# 5V-and-3V3-buck.net
KiCad netlist of a schematic drawn in Altium Designer
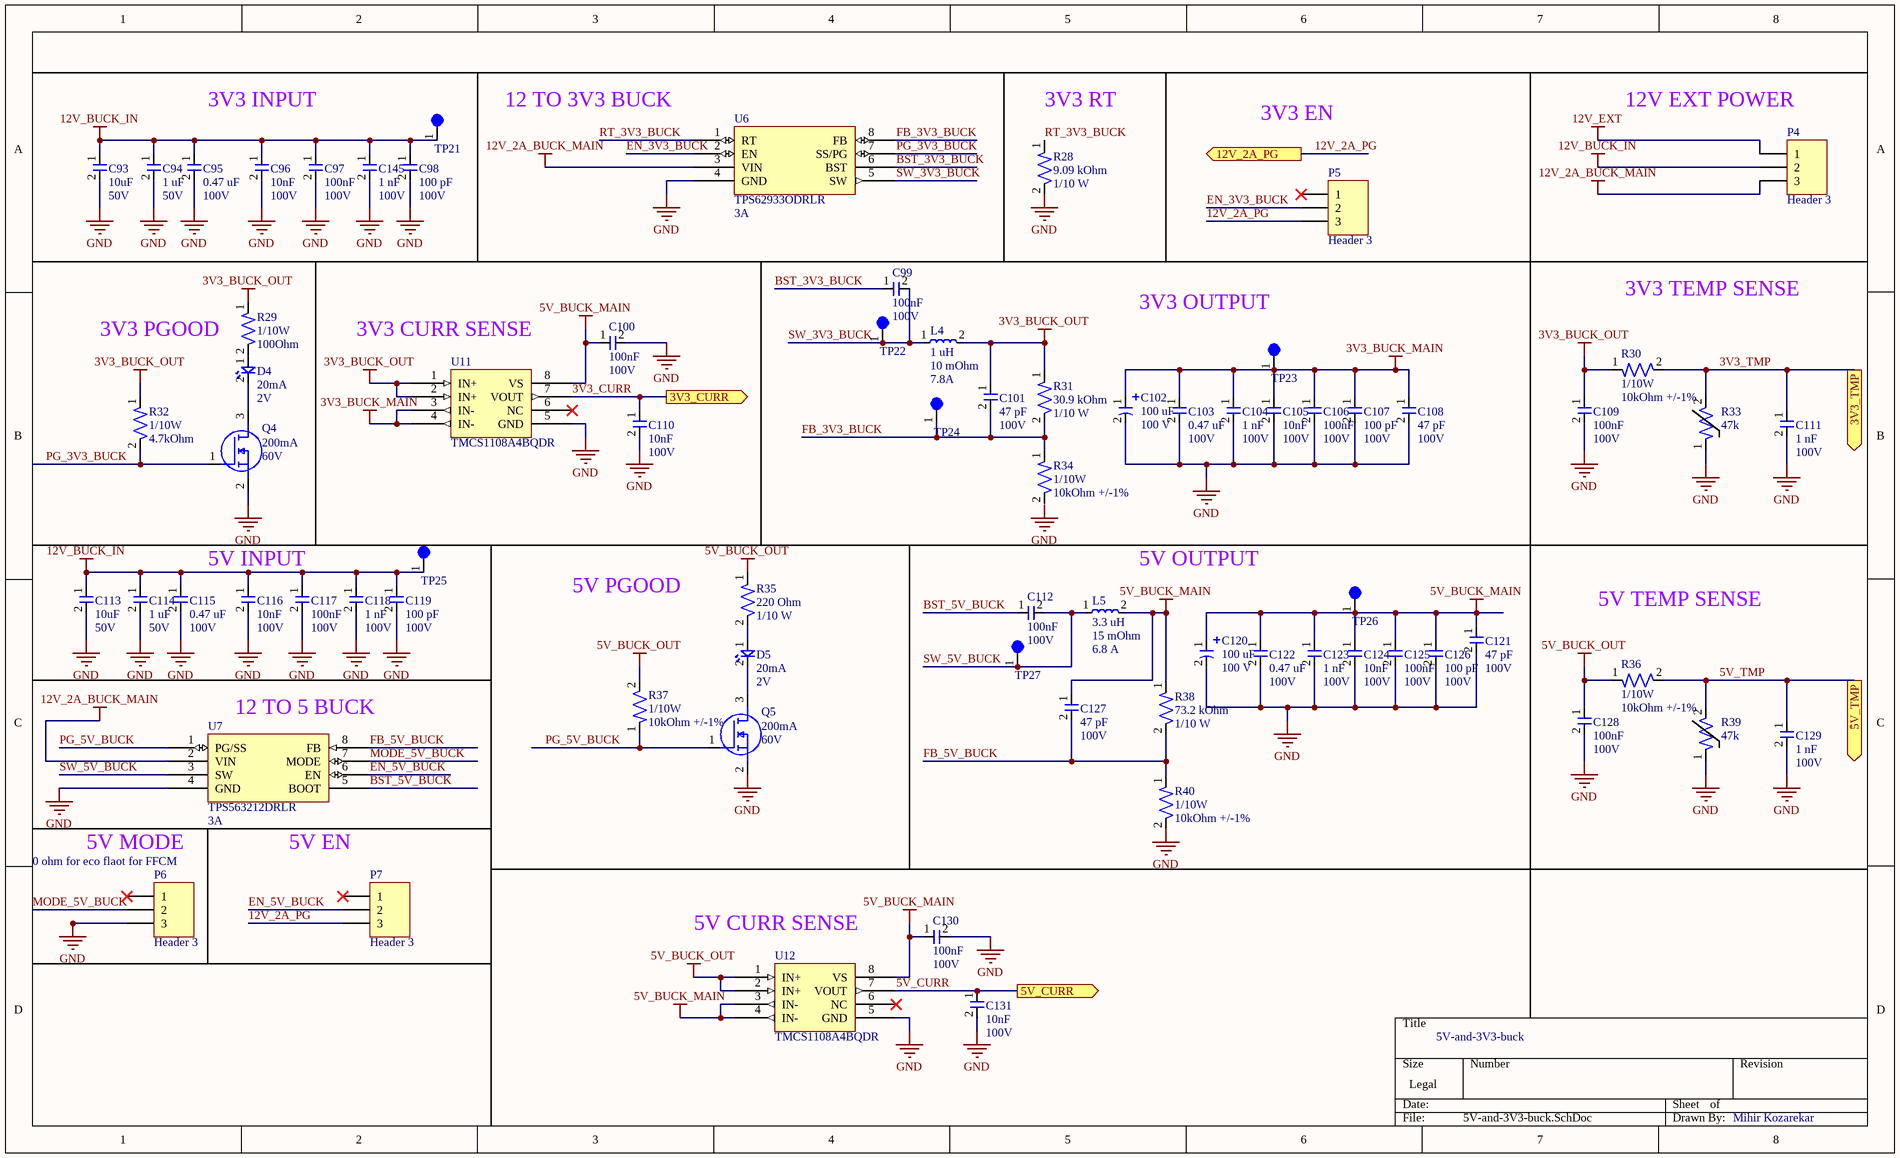
[diagram p0: 5V-and-3V3-buck.SchDoc]

(export (version "E")
  (design (tool "Eeschema 10.0.6"))
  (components
    (comp (ref "C93")
      (value "CL31B106KBHNNNE")
      (footprint "CAP-1206")
      (description "10 µF ±10% 50V Ceramic Capacitor X7R 1206 (3216 Metric)")
      (fields
        (field (name "MANUFACTURER") "Samsung Electro-Mechanics")
        (field (name "CAPACITANCE") "10uF")
        (field (name "VOLTAGE RATING") "50V")
      )
      (libsource (lib "MasterLib") (part "CAP-10U-0001"))
    )
    (comp (ref "C94")
      (value "UMK107AB7105KA-T")
      (footprint "CAP-0603")
      (description "1 µF ±10% 50V Ceramic Capacitor X7R 0603 (1608 Metric)")
      (fields (field (name "CAPACITANCE") "1 uF") (field (name "VOLTAGE") "50V"))
      (libsource (lib "MasterLib") (part "CAP-1U-0002"))
    )
    (comp (ref "C95")
      (value "KAM21KR72A474KL")
      (footprint "CAP-0805")
      (description "0.47 µF ±10% 100V Ceramic Capacitor X7R 0805 (2012 Metric)")
      (fields
        (field (name "TOLERANCE") "+/- 10%")
        (field (name "CAPACITANCE") "0.47 uF")
        (field (name "VOLTAGE") "100V")
      )
      (libsource (lib "MasterLib") (part "CAP-0.47U-0001"))
    )
    (comp (ref "C96")
      (value "C1608C0G2A103J080AC")
      (footprint "CAP-0603")
      (description "CAP CER 10000PF 100V C0G 0603")
      (fields
        (field (name "MANUFACTURER") "TDK Corporation")
        (field (name "CAPACITANCE") "10nF")
        (field (name "VOLTAGE RATING") "100V")
      )
      (libsource (lib "MasterLib") (part "CAP-10N-0002"))
    )
    (comp (ref "C97")
      (value "CC0603KRX7R0BB104")
      (footprint "CAP-0603")
      (description "CAP CER 0.1UF 100V X7R 0603")
      (fields
        (field (name "MANUFACTURER") "YAGEO")
        (field (name "CAPACITANCE") "100nF")
        (field (name "VOLTAGE RATING") "100V")
      )
      (libsource (lib "MasterLib") (part "CAP-100N-0001"))
    )
    (comp (ref "C98")
      (value "0603N101J101CT")
      (footprint "CAP-0603")
      (description "100 pF ±5% 100V Ceramic Capacitor C0G, NP0 0603 (1608 Metric)")
      (fields
        (field (name "TOLERANCE") "+/-5%")
        (field (name "CAPACITANCE") "100 pF")
        (field (name "VOLTAGE") "100V")
      )
      (libsource (lib "MasterLib") (part "CAP-100P-0002"))
    )
    (comp (ref "C99")
      (value "CC0603KRX7R0BB104")
      (footprint "CAP-0603")
      (description "CAP CER 0.1UF 100V X7R 0603")
      (fields
        (field (name "MANUFACTURER") "YAGEO")
        (field (name "CAPACITANCE") "100nF")
        (field (name "VOLTAGE RATING") "100V")
      )
      (libsource (lib "MasterLib") (part "CAP-100N-0001"))
    )
    (comp (ref "C100")
      (value "CC0603KRX7R0BB104")
      (footprint "CAP-0603")
      (description "CAP CER 0.1UF 100V X7R 0603")
      (fields
        (field (name "MANUFACTURER") "YAGEO")
        (field (name "CAPACITANCE") "100nF")
        (field (name "VOLTAGE RATING") "100V")
      )
      (libsource (lib "MasterLib") (part "CAP-100N-0001"))
    )
    (comp (ref "C101")
      (value "7447798111")
      (footprint "CAP-0603")
      (description "47 pF ±5% 100V Ceramic Capacitor C0G, NP0 0603 (1608 Metric)")
      (fields (field (name "CAPACITANCE") "47 pF") (field (name "VOLTAGE RATING") "100V"))
      (libsource (lib "MasterLib") (part "CAP-47P-0001"))
    )
    (comp (ref "C102")
      (value "100SEV100M12.5X16")
      (footprint "ELEC-100U-0001")
      (description "100 µF 100 V Aluminum Electrolytic Capacitors Radial, Can - SMD 2000 Hrs @ 85°C")
      (fields
        (field (name "MANUFACTURER") "Rubycon")
        (field (name "TOLERANCE") "+/- 20%")
        (field (name "CAPACITANCE") "100 uF")
        (field (name "VOLTAGE") "100 V")
      )
      (libsource (lib "MasterLib") (part "ELEC-100U-0001"))
    )
    (comp (ref "C103")
      (value "KAM21KR72A474KL")
      (footprint "CAP-0805")
      (description "0.47 µF ±10% 100V Ceramic Capacitor X7R 0805 (2012 Metric)")
      (fields
        (field (name "TOLERANCE") "+/- 10%")
        (field (name "CAPACITANCE") "0.47 uF")
        (field (name "VOLTAGE") "100V")
      )
      (libsource (lib "MasterLib") (part "CAP-0.47U-0001"))
    )
    (comp (ref "C104")
      (value "C0603Y102K1RAC7867")
      (footprint "CAP-0603")
      (description "1000 pF ±10% 100V Ceramic Capacitor X7R 0603 (1608 Metric)")
      (fields (field (name "CAPACITANCE") "1 nF") (field (name "VOLTAGE") "100V"))
      (libsource (lib "MasterLib") (part "CAP-1N-0001"))
    )
    (comp (ref "C105")
      (value "C1608C0G2A103J080AC")
      (footprint "CAP-0603")
      (description "CAP CER 10000PF 100V C0G 0603")
      (fields
        (field (name "MANUFACTURER") "TDK Corporation")
        (field (name "CAPACITANCE") "10nF")
        (field (name "VOLTAGE RATING") "100V")
      )
      (libsource (lib "MasterLib") (part "CAP-10N-0002"))
    )
    (comp (ref "C106")
      (value "CC0603KRX7R0BB104")
      (footprint "CAP-0603")
      (description "CAP CER 0.1UF 100V X7R 0603")
      (fields
        (field (name "MANUFACTURER") "YAGEO")
        (field (name "CAPACITANCE") "100nF")
        (field (name "VOLTAGE RATING") "100V")
      )
      (libsource (lib "MasterLib") (part "CAP-100N-0001"))
    )
    (comp (ref "C107")
      (value "0603N101J101CT")
      (footprint "CAP-0603")
      (description "100 pF ±5% 100V Ceramic Capacitor C0G, NP0 0603 (1608 Metric)")
      (fields
        (field (name "TOLERANCE") "+/-5%")
        (field (name "CAPACITANCE") "100 pF")
        (field (name "VOLTAGE") "100V")
      )
      (libsource (lib "MasterLib") (part "CAP-100P-0002"))
    )
    (comp (ref "C108")
      (value "7447798111")
      (footprint "CAP-0603")
      (description "47 pF ±5% 100V Ceramic Capacitor C0G, NP0 0603 (1608 Metric)")
      (fields (field (name "CAPACITANCE") "47 pF") (field (name "VOLTAGE RATING") "100V"))
      (libsource (lib "MasterLib") (part "CAP-47P-0001"))
    )
    (comp (ref "C109")
      (value "CC0603KRX7R0BB104")
      (footprint "CAP-0603")
      (description "CAP CER 0.1UF 100V X7R 0603")
      (fields
        (field (name "MANUFACTURER") "YAGEO")
        (field (name "CAPACITANCE") "100nF")
        (field (name "VOLTAGE RATING") "100V")
      )
      (libsource (lib "MasterLib") (part "CAP-100N-0001"))
    )
    (comp (ref "C110")
      (value "C1608C0G2A103J080AC")
      (footprint "CAP-0603")
      (description "CAP CER 10000PF 100V C0G 0603")
      (fields
        (field (name "MANUFACTURER") "TDK Corporation")
        (field (name "CAPACITANCE") "10nF")
        (field (name "VOLTAGE RATING") "100V")
      )
      (libsource (lib "MasterLib") (part "CAP-10N-0002"))
    )
    (comp (ref "C111")
      (value "C0603Y102K1RAC7867")
      (footprint "CAP-0603")
      (description "1000 pF ±10% 100V Ceramic Capacitor X7R 0603 (1608 Metric)")
      (fields (field (name "CAPACITANCE") "1 nF") (field (name "VOLTAGE") "100V"))
      (libsource (lib "MasterLib") (part "CAP-1N-0001"))
    )
    (comp (ref "C112")
      (value "CC0603KRX7R0BB104")
      (footprint "CAP-0603")
      (description "CAP CER 0.1UF 100V X7R 0603")
      (fields
        (field (name "MANUFACTURER") "YAGEO")
        (field (name "CAPACITANCE") "100nF")
        (field (name "VOLTAGE RATING") "100V")
      )
      (libsource (lib "MasterLib") (part "CAP-100N-0001"))
    )
    (comp (ref "C113")
      (value "CL31B106KBHNNNE")
      (footprint "CAP-1206")
      (description "10 µF ±10% 50V Ceramic Capacitor X7R 1206 (3216 Metric)")
      (fields
        (field (name "MANUFACTURER") "Samsung Electro-Mechanics")
        (field (name "CAPACITANCE") "10uF")
        (field (name "VOLTAGE RATING") "50V")
      )
      (libsource (lib "MasterLib") (part "CAP-10U-0001"))
    )
    (comp (ref "C114")
      (value "UMK107AB7105KA-T")
      (footprint "CAP-0603")
      (description "1 µF ±10% 50V Ceramic Capacitor X7R 0603 (1608 Metric)")
      (fields (field (name "CAPACITANCE") "1 uF") (field (name "VOLTAGE") "50V"))
      (libsource (lib "MasterLib") (part "CAP-1U-0002"))
    )
    (comp (ref "C115")
      (value "KAM21KR72A474KL")
      (footprint "CAP-0805")
      (description "0.47 µF ±10% 100V Ceramic Capacitor X7R 0805 (2012 Metric)")
      (fields
        (field (name "TOLERANCE") "+/- 10%")
        (field (name "CAPACITANCE") "0.47 uF")
        (field (name "VOLTAGE") "100V")
      )
      (libsource (lib "MasterLib") (part "CAP-0.47U-0001"))
    )
    (comp (ref "C116")
      (value "C1608C0G2A103J080AC")
      (footprint "CAP-0603")
      (description "CAP CER 10000PF 100V C0G 0603")
      (fields
        (field (name "MANUFACTURER") "TDK Corporation")
        (field (name "CAPACITANCE") "10nF")
        (field (name "VOLTAGE RATING") "100V")
      )
      (libsource (lib "MasterLib") (part "CAP-10N-0002"))
    )
    (comp (ref "C117")
      (value "CC0603KRX7R0BB104")
      (footprint "CAP-0603")
      (description "CAP CER 0.1UF 100V X7R 0603")
      (fields
        (field (name "MANUFACTURER") "YAGEO")
        (field (name "CAPACITANCE") "100nF")
        (field (name "VOLTAGE RATING") "100V")
      )
      (libsource (lib "MasterLib") (part "CAP-100N-0001"))
    )
    (comp (ref "C118")
      (value "C0603Y102K1RAC7867")
      (footprint "CAP-0603")
      (description "1000 pF ±10% 100V Ceramic Capacitor X7R 0603 (1608 Metric)")
      (fields (field (name "CAPACITANCE") "1 nF") (field (name "VOLTAGE") "100V"))
      (libsource (lib "MasterLib") (part "CAP-1N-0001"))
    )
    (comp (ref "C119")
      (value "0603N101J101CT")
      (footprint "CAP-0603")
      (description "100 pF ±5% 100V Ceramic Capacitor C0G, NP0 0603 (1608 Metric)")
      (fields
        (field (name "TOLERANCE") "+/-5%")
        (field (name "CAPACITANCE") "100 pF")
        (field (name "VOLTAGE") "100V")
      )
      (libsource (lib "MasterLib") (part "CAP-100P-0002"))
    )
    (comp (ref "C120")
      (value "100SEV100M12.5X16")
      (footprint "ELEC-100U-0001")
      (description "100 µF 100 V Aluminum Electrolytic Capacitors Radial, Can - SMD 2000 Hrs @ 85°C")
      (fields
        (field (name "MANUFACTURER") "Rubycon")
        (field (name "TOLERANCE") "+/- 20%")
        (field (name "CAPACITANCE") "100 uF")
        (field (name "VOLTAGE") "100 V")
      )
      (libsource (lib "MasterLib") (part "ELEC-100U-0001"))
    )
    (comp (ref "C121")
      (value "7447798111")
      (footprint "CAP-0603")
      (description "47 pF ±5% 100V Ceramic Capacitor C0G, NP0 0603 (1608 Metric)")
      (fields (field (name "CAPACITANCE") "47 pF") (field (name "VOLTAGE RATING") "100V"))
      (libsource (lib "MasterLib") (part "CAP-47P-0001"))
    )
    (comp (ref "C122")
      (value "KAM21KR72A474KL")
      (footprint "CAP-0805")
      (description "0.47 µF ±10% 100V Ceramic Capacitor X7R 0805 (2012 Metric)")
      (fields
        (field (name "TOLERANCE") "+/- 10%")
        (field (name "CAPACITANCE") "0.47 uF")
        (field (name "VOLTAGE") "100V")
      )
      (libsource (lib "MasterLib") (part "CAP-0.47U-0001"))
    )
    (comp (ref "C123")
      (value "C0603Y102K1RAC7867")
      (footprint "CAP-0603")
      (description "1000 pF ±10% 100V Ceramic Capacitor X7R 0603 (1608 Metric)")
      (fields (field (name "CAPACITANCE") "1 nF") (field (name "VOLTAGE") "100V"))
      (libsource (lib "MasterLib") (part "CAP-1N-0001"))
    )
    (comp (ref "C124")
      (value "C1608C0G2A103J080AC")
      (footprint "CAP-0603")
      (description "CAP CER 10000PF 100V C0G 0603")
      (fields
        (field (name "MANUFACTURER") "TDK Corporation")
        (field (name "CAPACITANCE") "10nF")
        (field (name "VOLTAGE RATING") "100V")
      )
      (libsource (lib "MasterLib") (part "CAP-10N-0002"))
    )
    (comp (ref "C125")
      (value "CC0603KRX7R0BB104")
      (footprint "CAP-0603")
      (description "CAP CER 0.1UF 100V X7R 0603")
      (fields
        (field (name "MANUFACTURER") "YAGEO")
        (field (name "CAPACITANCE") "100nF")
        (field (name "VOLTAGE RATING") "100V")
      )
      (libsource (lib "MasterLib") (part "CAP-100N-0001"))
    )
    (comp (ref "C126")
      (value "0603N101J101CT")
      (footprint "CAP-0603")
      (description "100 pF ±5% 100V Ceramic Capacitor C0G, NP0 0603 (1608 Metric)")
      (fields
        (field (name "TOLERANCE") "+/-5%")
        (field (name "CAPACITANCE") "100 pF")
        (field (name "VOLTAGE") "100V")
      )
      (libsource (lib "MasterLib") (part "CAP-100P-0002"))
    )
    (comp (ref "C127")
      (value "7447798111")
      (footprint "CAP-0603")
      (description "47 pF ±5% 100V Ceramic Capacitor C0G, NP0 0603 (1608 Metric)")
      (fields (field (name "CAPACITANCE") "47 pF") (field (name "VOLTAGE RATING") "100V"))
      (libsource (lib "MasterLib") (part "CAP-47P-0001"))
    )
    (comp (ref "C128")
      (value "CC0603KRX7R0BB104")
      (footprint "CAP-0603")
      (description "CAP CER 0.1UF 100V X7R 0603")
      (fields
        (field (name "MANUFACTURER") "YAGEO")
        (field (name "CAPACITANCE") "100nF")
        (field (name "VOLTAGE RATING") "100V")
      )
      (libsource (lib "MasterLib") (part "CAP-100N-0001"))
    )
    (comp (ref "C129")
      (value "C0603Y102K1RAC7867")
      (footprint "CAP-0603")
      (description "1000 pF ±10% 100V Ceramic Capacitor X7R 0603 (1608 Metric)")
      (fields (field (name "CAPACITANCE") "1 nF") (field (name "VOLTAGE") "100V"))
      (libsource (lib "MasterLib") (part "CAP-1N-0001"))
    )
    (comp (ref "C130")
      (value "CC0603KRX7R0BB104")
      (footprint "CAP-0603")
      (description "CAP CER 0.1UF 100V X7R 0603")
      (fields
        (field (name "MANUFACTURER") "YAGEO")
        (field (name "CAPACITANCE") "100nF")
        (field (name "VOLTAGE RATING") "100V")
      )
      (libsource (lib "MasterLib") (part "CAP-100N-0001"))
    )
    (comp (ref "C131")
      (value "C1608C0G2A103J080AC")
      (footprint "CAP-0603")
      (description "CAP CER 10000PF 100V C0G 0603")
      (fields
        (field (name "MANUFACTURER") "TDK Corporation")
        (field (name "CAPACITANCE") "10nF")
        (field (name "VOLTAGE RATING") "100V")
      )
      (libsource (lib "MasterLib") (part "CAP-10N-0002"))
    )
    (comp (ref "C145")
      (value "C0603Y102K1RAC7867")
      (footprint "CAP-0603")
      (description "1000 pF ±10% 100V Ceramic Capacitor X7R 0603 (1608 Metric)")
      (fields (field (name "CAPACITANCE") "1 nF") (field (name "VOLTAGE") "100V"))
      (libsource (lib "MasterLib") (part "CAP-1N-0001"))
    )
    (comp (ref "D4")
      (value "150060AS75000")
      (footprint "LED-0603")
      (description "CAP CER 0.1UF 100V X7R 0603")
      (fields
        (field (name "MANUFACTURER") "Wurth Electronik")
        (field (name "CURRENT RATING") "20mA")
        (field (name "VF") "2V")
      )
      (libsource (lib "MasterLib") (part "LED_Amber_0001"))
    )
    (comp (ref "D5")
      (value "150060AS75000")
      (footprint "LED-0603")
      (description "CAP CER 0.1UF 100V X7R 0603")
      (fields
        (field (name "MANUFACTURER") "Wurth Electronik")
        (field (name "CURRENT RATING") "20mA")
        (field (name "VF") "2V")
      )
      (libsource (lib "MasterLib") (part "LED_Amber_0001"))
    )
    (comp (ref "L4")
      (value "SRN8040-1R0Y")
      (footprint "PWRIND-6.8U-0001")
      (description "1 µH Semi-Shielded Drum Core, Wirewound Inductor 7.8 A 10mOhm Max Nonstandard")
      (fields
        (field (name "TOLERANCE") "30%")
        (field (name "INDUCTANCE") "1 uH")
        (field (name "DCR") "10 mOhm")
        (field (name "DCI") "7.8A")
      )
      (libsource (lib "MasterLib") (part "PWRIND-1U-0001"))
    )
    (comp (ref "L5")
      (value "SRR1240-3R3Y")
      (footprint "PWRIND-3.3U-0003")
      (description "3.3 µH Shielded Drum Core, Wirewound Inductor 6.8 A 15mOhm Max Nonstandard")
      (fields
        (field (name "TOLERANCE") "30%")
        (field (name "INDUCTANCE") "3.3 uH")
        (field (name "DCR") "15 mOhm")
        (field (name "DCI") "6.8 A")
      )
      (libsource (lib "MasterLib") (part "PWRIND-3.3U-0003"))
    )
    (comp (ref "P4")
      (value "Header 3")
      (footprint "HDR1X3")
      (description "Header, 3-Pin")
      (fields (field (name "PUBLISHER") "Altium Limited"))
      (libsource (lib "Miscellaneous Connectors") (part "Header 3"))
    )
    (comp (ref "P5")
      (value "Header 3")
      (footprint "HDR1X3")
      (description "Header, 3-Pin")
      (fields (field (name "PUBLISHER") "Altium Limited"))
      (libsource (lib "Miscellaneous Connectors") (part "Header 3"))
    )
    (comp (ref "P6")
      (value "Header 3")
      (footprint "HDR1X3")
      (description "Header, 3-Pin")
      (fields (field (name "PUBLISHER") "Altium Limited"))
      (libsource (lib "Miscellaneous Connectors") (part "Header 3"))
    )
    (comp (ref "P7")
      (value "Header 3")
      (footprint "HDR1X3")
      (description "Header, 3-Pin")
      (fields (field (name "PUBLISHER") "Altium Limited"))
      (libsource (lib "Miscellaneous Connectors") (part "Header 3"))
    )
    (comp (ref "Q4")
      (value "T2N7002AK,LM")
      (footprint "NMOS-SOT23-3")
      (description "MOSFET N-CH 60V 200MA SOT23")
      (fields
        (field (name "MANUFACTURER") "Toshiba")
        (field (name "ID-CONTINUOUS") "200mA")
        (field (name "VDS-MAX") "60V")
      )
      (libsource (lib "MasterLib") (part "NMOS-200MA-0001"))
    )
    (comp (ref "Q5")
      (value "T2N7002AK,LM")
      (footprint "NMOS-SOT23-3")
      (description "MOSFET N-CH 60V 200MA SOT23")
      (fields
        (field (name "MANUFACTURER") "Toshiba")
        (field (name "ID-CONTINUOUS") "200mA")
        (field (name "VDS-MAX") "60V")
      )
      (libsource (lib "MasterLib") (part "NMOS-200MA-0001"))
    )
    (comp (ref "R28")
      (value "RC0603FR-079K09L")
      (footprint "RES-0603")
      (description "9.09 kOhms ±1% 0.1W, 1/10W Chip Resistor 0603 (1608 Metric) Moisture Resistant Thick Film")
      (fields
        (field (name "TOLERANCE") "+/-1%")
        (field (name "RESISTANCE") "9.09 kOhm")
        (field (name "POWER") "1/10 W")
      )
      (libsource (lib "MasterLib") (part "RES-9.09K-0001"))
    )
    (comp (ref "R29")
      (value "AC0603FR-10100RL")
      (footprint "RES-0603")
      (description "100 Ohms ±1% 0.1W, 1/10W Chip Resistor 0603 (1608 Metric) Automotive AEC-Q200 Thick Film")
      (fields
        (field (name "MANUFACTURER") "YAGEO")
        (field (name "POWER RATING") "1/10W")
        (field (name "RESISTANCE") "100Ohm")
      )
      (libsource (lib "MasterLib") (part "RES-100-0002"))
    )
    (comp (ref "R30")
      (value "RC0603FR-0710KP")
      (footprint "RES-0603")
      (description "RES SMD 10K OHM 1% 1/10W 0603")
      (fields
        (field (name "MANUFACTURER") "YAGEO")
        (field (name "POWER RATING") "1/10W")
        (field (name "RESISTANCE") "10kOhm +/-1%")
      )
      (libsource (lib "MasterLib") (part "RES-10K-0002"))
    )
    (comp (ref "R31")
      (value "RC0603FR-0730K9L")
      (footprint "RES-0603")
      (description "30.9 kOhms ±1% 0.1W, 1/10W Chip Resistor 0603 (1608 Metric) Moisture Resistant Thick Film")
      (fields
        (field (name "TOLERANCE") "1%")
        (field (name "RESISTANCE") "30.9 kOhm")
        (field (name "POWER") "1/10 W")
      )
      (libsource (lib "MasterLib") (part "RES-30.9K-0001"))
    )
    (comp (ref "R32")
      (value "AF0603FR-074K7L")
      (footprint "RES-0603")
      (description "RES SMD 4.7K OHM 1% 1/10W 0603")
      (fields
        (field (name "MANUFACTURER") "YAGEO")
        (field (name "POWER RATING") "1/10W")
        (field (name "RESISTANCE") "4.7kOhm")
      )
      (libsource (lib "MasterLib") (part "RES-4.7K-0002"))
    )
    (comp (ref "R33")
      (value "TMP6431DECR")
      (footprint "RES-0402")
      (description "PTC Thermistor 47 kOhms 0402 (1006 Metric)")
      (fields (field (name "MANUFACTURER") "Texas Instruments") (field (name "RESISTANCE") "47k"))
      (libsource (lib "MasterLib") (part "THERM-47K-0001"))
    )
    (comp (ref "R34")
      (value "RC0603FR-0710KP")
      (footprint "RES-0603")
      (description "RES SMD 10K OHM 1% 1/10W 0603")
      (fields
        (field (name "MANUFACTURER") "YAGEO")
        (field (name "POWER RATING") "1/10W")
        (field (name "RESISTANCE") "10kOhm +/-1%")
      )
      (libsource (lib "MasterLib") (part "RES-10K-0002"))
    )
    (comp (ref "R35")
      (value "CRGCQ0603J220R")
      (footprint "RES-0603")
      (fields
        (field (name "TOLERANCE") "+/- 5%")
        (field (name "RESISTANCE") "220 Ohm")
        (field (name "POWER") "1/10 W")
      )
      (libsource (lib "MasterLib") (part "RES-220-003"))
    )
    (comp (ref "R36")
      (value "RC0603FR-0710KP")
      (footprint "RES-0603")
      (description "RES SMD 10K OHM 1% 1/10W 0603")
      (fields
        (field (name "MANUFACTURER") "YAGEO")
        (field (name "POWER RATING") "1/10W")
        (field (name "RESISTANCE") "10kOhm +/-1%")
      )
      (libsource (lib "MasterLib") (part "RES-10K-0002"))
    )
    (comp (ref "R37")
      (value "RC0603FR-0710KP")
      (footprint "RES-0603")
      (description "RES SMD 10K OHM 1% 1/10W 0603")
      (fields
        (field (name "MANUFACTURER") "YAGEO")
        (field (name "POWER RATING") "1/10W")
        (field (name "RESISTANCE") "10kOhm +/-1%")
      )
      (libsource (lib "MasterLib") (part "RES-10K-0002"))
    )
    (comp (ref "R38")
      (value "RC0603FR-0773K2L")
      (footprint "RES-0603")
      (description "73.2 kOhms ±1% 0.1W, 1/10W Chip Resistor 0603 (1608 Metric) Moisture Resistant Thick Film")
      (fields
        (field (name "TOLERANCE") "1%")
        (field (name "RESISTANCE") "73.2 kOhm")
        (field (name "POWER") "1/10 W")
      )
      (libsource (lib "MasterLib") (part "RES-73.2K-0001"))
    )
    (comp (ref "R39")
      (value "TMP6431DECR")
      (footprint "RES-0402")
      (description "PTC Thermistor 47 kOhms 0402 (1006 Metric)")
      (fields (field (name "MANUFACTURER") "Texas Instruments") (field (name "RESISTANCE") "47k"))
      (libsource (lib "MasterLib") (part "THERM-47K-0001"))
    )
    (comp (ref "R40")
      (value "RC0603FR-0710KP")
      (footprint "RES-0603")
      (description "RES SMD 10K OHM 1% 1/10W 0603")
      (fields
        (field (name "MANUFACTURER") "YAGEO")
        (field (name "POWER RATING") "1/10W")
        (field (name "RESISTANCE") "10kOhm +/-1%")
      )
      (libsource (lib "MasterLib") (part "RES-10K-0002"))
    )
    (comp (ref "TP21")
      (value "5003")
      (footprint "TEST-POINT-0001")
      (description "Oranange PC Test Point, Miniature Phoisphor Bronze Silver Plating Through Hole Mounting Type")
      (libsource (lib "MasterLib") (part "TEST-POINT-0001"))
    )
    (comp (ref "TP22")
      (value "5003")
      (footprint "TEST-POINT-0001")
      (description "Oranange PC Test Point, Miniature Phoisphor Bronze Silver Plating Through Hole Mounting Type")
      (libsource (lib "MasterLib") (part "TEST-POINT-0001"))
    )
    (comp (ref "TP23")
      (value "5003")
      (footprint "TEST-POINT-0001")
      (description "Oranange PC Test Point, Miniature Phoisphor Bronze Silver Plating Through Hole Mounting Type")
      (libsource (lib "MasterLib") (part "TEST-POINT-0001"))
    )
    (comp (ref "TP24")
      (value "5003")
      (footprint "TEST-POINT-0001")
      (description "Oranange PC Test Point, Miniature Phoisphor Bronze Silver Plating Through Hole Mounting Type")
      (libsource (lib "MasterLib") (part "TEST-POINT-0001"))
    )
    (comp (ref "TP25")
      (value "5003")
      (footprint "TEST-POINT-0001")
      (description "Oranange PC Test Point, Miniature Phoisphor Bronze Silver Plating Through Hole Mounting Type")
      (libsource (lib "MasterLib") (part "TEST-POINT-0001"))
    )
    (comp (ref "TP26")
      (value "5003")
      (footprint "TEST-POINT-0001")
      (description "Oranange PC Test Point, Miniature Phoisphor Bronze Silver Plating Through Hole Mounting Type")
      (libsource (lib "MasterLib") (part "TEST-POINT-0001"))
    )
    (comp (ref "TP27")
      (value "5003")
      (footprint "TEST-POINT-0001")
      (description "Oranange PC Test Point, Miniature Phoisphor Bronze Silver Plating Through Hole Mounting Type")
      (libsource (lib "MasterLib") (part "TEST-POINT-0001"))
    )
    (comp (ref "U6")
      (value "TPS62933ODRLR")
      (footprint "IC-SOT583")
      (description "Buck Switching Regulator IC Positive Adjustable 0.8V 1 Output 3A SOT-583")
      (fields (field (name "MANUFACTURER") "Texas Instruments") (field (name "CURRENT") "3A"))
      (libsource (lib "MasterLib") (part "IC-BUCK-0010"))
    )
    (comp (ref "U7")
      (value "TPS563212DRLR")
      (footprint "IC-SOT583")
      (description "Buck Switching Regulator IC Positive Adjustable 0.6V 1 Output 3A SOT-583")
      (fields (field (name "MANUFACTURER") "Texaas Instruments") (field (name "CURRENT") "3A"))
      (libsource (lib "MasterLib") (part "IC-BUCK-0008"))
    )
    (comp (ref "U11")
      (value "TMCS1108A4BQDR")
      (footprint "IC-CURRENT-0001")
      (description "Current Sensor 1 Channel Hall Effect Bidirectional 8-SOIC (0.154\", 3.90mm Width)")
      (libsource (lib "MasterLib") (part "IC-CURRENT-0004"))
    )
    (comp (ref "U12")
      (value "TMCS1108A4BQDR")
      (footprint "IC-CURRENT-0001")
      (description "Current Sensor 1 Channel Hall Effect Bidirectional 8-SOIC (0.154\", 3.90mm Width)")
      (libsource (lib "MasterLib") (part "IC-CURRENT-0004"))
    )
  )
  (nets
    (net (code "1") (name "/3V3_CURR") (class "Default")
      (node (ref "C110") (pin "1") (pinfunction "1_1") (pintype "passive"))
      (node (ref "U11") (pin "7") (pinfunction "VOUT_7") (pintype "output"))
    )
    (net (code "2") (name "/3V3_TMP") (class "Default")
      (node (ref "C111") (pin "1") (pinfunction "1_1") (pintype "passive"))
      (node (ref "R30") (pin "2") (pinfunction "2_2") (pintype "passive"))
      (node (ref "R33") (pin "2") (pinfunction "2_2") (pintype "passive"))
    )
    (net (code "3") (name "/5V_CURR") (class "Default")
      (node (ref "C131") (pin "1") (pinfunction "1_1") (pintype "passive"))
      (node (ref "U12") (pin "7") (pinfunction "VOUT_7") (pintype "output"))
    )
    (net (code "4") (name "/5V_TMP") (class "Default")
      (node (ref "C129") (pin "1") (pinfunction "1_1") (pintype "passive"))
      (node (ref "R36") (pin "2") (pinfunction "2_2") (pintype "passive"))
      (node (ref "R39") (pin "2") (pinfunction "2_2") (pintype "passive"))
    )
    (net (code "5") (name "/12V_2A_PG") (class "Default")
      (node (ref "P5") (pin "3") (pinfunction "3_3") (pintype "passive"))
      (node (ref "P7") (pin "3") (pinfunction "3_3") (pintype "passive"))
    )
    (net (code "6") (name "/BST_3V3_BUCK") (class "Default")
      (node (ref "C99") (pin "1") (pinfunction "1_1") (pintype "passive"))
      (node (ref "U6") (pin "6") (pinfunction "BST_6") (pintype "power_in"))
    )
    (net (code "7") (name "/BST_5V_BUCK") (class "Default")
      (node (ref "C112") (pin "1") (pinfunction "1_1") (pintype "passive"))
      (node (ref "U7") (pin "5") (pinfunction "BOOT_5") (pintype "power_in"))
    )
    (net (code "8") (name "/EN_3V3_BUCK") (class "Default")
      (node (ref "P5") (pin "2") (pinfunction "2_2") (pintype "passive"))
      (node (ref "U6") (pin "2") (pinfunction "EN_2") (pintype "bidirectional"))
    )
    (net (code "9") (name "/EN_5V_BUCK") (class "Default")
      (node (ref "P7") (pin "2") (pinfunction "2_2") (pintype "passive"))
      (node (ref "U7") (pin "6") (pinfunction "EN_6") (pintype "bidirectional"))
    )
    (net (code "10") (name "/FB_3V3_BUCK") (class "Default")
      (node (ref "C101") (pin "2") (pinfunction "2_2") (pintype "passive"))
      (node (ref "R31") (pin "2") (pinfunction "2_2") (pintype "passive"))
      (node (ref "R34") (pin "1") (pinfunction "1_1") (pintype "passive"))
      (node (ref "TP24") (pin "1") (pinfunction "0_1") (pintype "passive"))
      (node (ref "U6") (pin "8") (pinfunction "FB_8") (pintype "bidirectional"))
    )
    (net (code "11") (name "/FB_5V_BUCK") (class "Default")
      (node (ref "C127") (pin "2") (pinfunction "2_2") (pintype "passive"))
      (node (ref "R38") (pin "2") (pinfunction "2_2") (pintype "passive"))
      (node (ref "R40") (pin "1") (pinfunction "1_1") (pintype "passive"))
      (node (ref "U7") (pin "8") (pinfunction "FB_8") (pintype "input"))
    )
    (net (code "12") (name "/MODE_5V_BUCK") (class "Default")
      (node (ref "P6") (pin "2") (pinfunction "2_2") (pintype "passive"))
      (node (ref "U7") (pin "7") (pinfunction "MODE_7") (pintype "bidirectional"))
    )
    (net (code "13") (name "/PG_3V3_BUCK") (class "Default")
      (node (ref "Q4") (pin "1") (pinfunction "G_1") (pintype "passive"))
      (node (ref "R32") (pin "2") (pinfunction "2_2") (pintype "passive"))
      (node (ref "U6") (pin "7") (pinfunction "SS/PG_7") (pintype "bidirectional"))
    )
    (net (code "14") (name "/PG_5V_BUCK") (class "Default")
      (node (ref "Q5") (pin "1") (pinfunction "G_1") (pintype "passive"))
      (node (ref "R37") (pin "1") (pinfunction "1_1") (pintype "passive"))
      (node (ref "U7") (pin "1") (pinfunction "PG/SS_1") (pintype "bidirectional"))
    )
    (net (code "15") (name "/RT_3V3_BUCK") (class "Default")
      (node (ref "R28") (pin "1") (pinfunction "1_1") (pintype "passive"))
      (node (ref "U6") (pin "1") (pinfunction "RT_1") (pintype "bidirectional"))
    )
    (net (code "16") (name "/SW_3V3_BUCK") (class "Default")
      (node (ref "C99") (pin "2") (pinfunction "2_2") (pintype "passive"))
      (node (ref "L4") (pin "1") (pinfunction "1_1") (pintype "passive"))
      (node (ref "TP22") (pin "1") (pinfunction "0_1") (pintype "passive"))
      (node (ref "U6") (pin "5") (pinfunction "SW_5") (pintype "output"))
    )
    (net (code "17") (name "/SW_5V_BUCK") (class "Default")
      (node (ref "C112") (pin "2") (pinfunction "2_2") (pintype "passive"))
      (node (ref "L5") (pin "1") (pinfunction "1_1") (pintype "passive"))
      (node (ref "TP27") (pin "1") (pinfunction "0_1") (pintype "passive"))
      (node (ref "U7") (pin "3") (pinfunction "SW_3") (pintype "power_in"))
    )
    (net (code "18") (name "3V3_BUCK_MAIN") (class "Default")
      (node (ref "C102") (pin "1") (pinfunction "1_1") (pintype "passive"))
      (node (ref "C103") (pin "1") (pinfunction "1_1") (pintype "passive"))
      (node (ref "C104") (pin "1") (pinfunction "1_1") (pintype "passive"))
      (node (ref "C105") (pin "1") (pinfunction "1_1") (pintype "passive"))
      (node (ref "C106") (pin "1") (pinfunction "1_1") (pintype "passive"))
      (node (ref "C107") (pin "1") (pinfunction "1_1") (pintype "passive"))
      (node (ref "C108") (pin "1") (pinfunction "1_1") (pintype "passive"))
      (node (ref "TP23") (pin "1") (pinfunction "0_1") (pintype "passive"))
      (node (ref "U11") (pin "3") (pinfunction "IN-_3") (pintype "output"))
      (node (ref "U11") (pin "4") (pinfunction "IN-_4") (pintype "output"))
    )
    (net (code "19") (name "3V3_BUCK_OUT") (class "Default")
      (node (ref "C101") (pin "1") (pinfunction "1_1") (pintype "passive"))
      (node (ref "C109") (pin "1") (pinfunction "1_1") (pintype "passive"))
      (node (ref "L4") (pin "2") (pinfunction "2_2") (pintype "passive"))
      (node (ref "R29") (pin "1") (pinfunction "1_1") (pintype "passive"))
      (node (ref "R30") (pin "1") (pinfunction "1_1") (pintype "passive"))
      (node (ref "R31") (pin "1") (pinfunction "1_1") (pintype "passive"))
      (node (ref "R32") (pin "1") (pinfunction "1_1") (pintype "passive"))
      (node (ref "U11") (pin "1") (pinfunction "IN+_1") (pintype "input"))
      (node (ref "U11") (pin "2") (pinfunction "IN+_2") (pintype "input"))
    )
    (net (code "20") (name "5V_BUCK_MAIN") (class "Default")
      (node (ref "C100") (pin "1") (pinfunction "1_1") (pintype "passive"))
      (node (ref "C120") (pin "1") (pinfunction "1_1") (pintype "passive"))
      (node (ref "C121") (pin "1") (pinfunction "1_1") (pintype "passive"))
      (node (ref "C122") (pin "1") (pinfunction "1_1") (pintype "passive"))
      (node (ref "C123") (pin "1") (pinfunction "1_1") (pintype "passive"))
      (node (ref "C124") (pin "1") (pinfunction "1_1") (pintype "passive"))
      (node (ref "C125") (pin "1") (pinfunction "1_1") (pintype "passive"))
      (node (ref "C126") (pin "1") (pinfunction "1_1") (pintype "passive"))
      (node (ref "C127") (pin "1") (pinfunction "1_1") (pintype "passive"))
      (node (ref "C130") (pin "1") (pinfunction "1_1") (pintype "passive"))
      (node (ref "L5") (pin "2") (pinfunction "2_2") (pintype "passive"))
      (node (ref "R38") (pin "1") (pinfunction "1_1") (pintype "passive"))
      (node (ref "TP26") (pin "1") (pinfunction "0_1") (pintype "passive"))
      (node (ref "U11") (pin "8") (pinfunction "VS_8") (pintype "power_in"))
      (node (ref "U12") (pin "3") (pinfunction "IN-_3") (pintype "output"))
      (node (ref "U12") (pin "4") (pinfunction "IN-_4") (pintype "output"))
      (node (ref "U12") (pin "8") (pinfunction "VS_8") (pintype "power_in"))
    )
    (net (code "21") (name "5V_BUCK_OUT") (class "Default")
      (node (ref "C128") (pin "1") (pinfunction "1_1") (pintype "passive"))
      (node (ref "R35") (pin "1") (pinfunction "1_1") (pintype "passive"))
      (node (ref "R36") (pin "1") (pinfunction "1_1") (pintype "passive"))
      (node (ref "R37") (pin "2") (pinfunction "2_2") (pintype "passive"))
      (node (ref "U12") (pin "1") (pinfunction "IN+_1") (pintype "input"))
      (node (ref "U12") (pin "2") (pinfunction "IN+_2") (pintype "input"))
    )
    (net (code "22") (name "12V_2A_BUCK_MAIN") (class "Default")
      (node (ref "P4") (pin "3") (pinfunction "3_3") (pintype "passive"))
      (node (ref "U6") (pin "3") (pinfunction "VIN_3") (pintype "power_in"))
      (node (ref "U7") (pin "2") (pinfunction "VIN_2") (pintype "power_in"))
    )
    (net (code "23") (name "12V_BUCK_IN") (class "Default")
      (node (ref "C113") (pin "1") (pinfunction "1_1") (pintype "passive"))
      (node (ref "C114") (pin "1") (pinfunction "1_1") (pintype "passive"))
      (node (ref "C115") (pin "1") (pinfunction "1_1") (pintype "passive"))
      (node (ref "C116") (pin "1") (pinfunction "1_1") (pintype "passive"))
      (node (ref "C117") (pin "1") (pinfunction "1_1") (pintype "passive"))
      (node (ref "C118") (pin "1") (pinfunction "1_1") (pintype "passive"))
      (node (ref "C119") (pin "1") (pinfunction "1_1") (pintype "passive"))
      (node (ref "C145") (pin "1") (pinfunction "1_1") (pintype "passive"))
      (node (ref "C93") (pin "1") (pinfunction "1_1") (pintype "passive"))
      (node (ref "C94") (pin "1") (pinfunction "1_1") (pintype "passive"))
      (node (ref "C95") (pin "1") (pinfunction "1_1") (pintype "passive"))
      (node (ref "C96") (pin "1") (pinfunction "1_1") (pintype "passive"))
      (node (ref "C97") (pin "1") (pinfunction "1_1") (pintype "passive"))
      (node (ref "C98") (pin "1") (pinfunction "1_1") (pintype "passive"))
      (node (ref "P4") (pin "2") (pinfunction "2_2") (pintype "passive"))
      (node (ref "TP21") (pin "1") (pinfunction "0_1") (pintype "passive"))
      (node (ref "TP25") (pin "1") (pinfunction "0_1") (pintype "passive"))
    )
    (net (code "24") (name "12V_EXT") (class "Default")
      (node (ref "P4") (pin "1") (pinfunction "1_1") (pintype "passive"))
    )
    (net (code "25") (name "GND") (class "Default")
      (node (ref "C100") (pin "2") (pinfunction "2_2") (pintype "passive"))
      (node (ref "C102") (pin "2") (pinfunction "2_2") (pintype "passive"))
      (node (ref "C103") (pin "2") (pinfunction "2_2") (pintype "passive"))
      (node (ref "C104") (pin "2") (pinfunction "2_2") (pintype "passive"))
      (node (ref "C105") (pin "2") (pinfunction "2_2") (pintype "passive"))
      (node (ref "C106") (pin "2") (pinfunction "2_2") (pintype "passive"))
      (node (ref "C107") (pin "2") (pinfunction "2_2") (pintype "passive"))
      (node (ref "C108") (pin "2") (pinfunction "2_2") (pintype "passive"))
      (node (ref "C109") (pin "2") (pinfunction "2_2") (pintype "passive"))
      (node (ref "C110") (pin "2") (pinfunction "2_2") (pintype "passive"))
      (node (ref "C111") (pin "2") (pinfunction "2_2") (pintype "passive"))
      (node (ref "C113") (pin "2") (pinfunction "2_2") (pintype "passive"))
      (node (ref "C114") (pin "2") (pinfunction "2_2") (pintype "passive"))
      (node (ref "C115") (pin "2") (pinfunction "2_2") (pintype "passive"))
      (node (ref "C116") (pin "2") (pinfunction "2_2") (pintype "passive"))
      (node (ref "C117") (pin "2") (pinfunction "2_2") (pintype "passive"))
      (node (ref "C118") (pin "2") (pinfunction "2_2") (pintype "passive"))
      (node (ref "C119") (pin "2") (pinfunction "2_2") (pintype "passive"))
      (node (ref "C120") (pin "2") (pinfunction "2_2") (pintype "passive"))
      (node (ref "C121") (pin "2") (pinfunction "2_2") (pintype "passive"))
      (node (ref "C122") (pin "2") (pinfunction "2_2") (pintype "passive"))
      (node (ref "C123") (pin "2") (pinfunction "2_2") (pintype "passive"))
      (node (ref "C124") (pin "2") (pinfunction "2_2") (pintype "passive"))
      (node (ref "C125") (pin "2") (pinfunction "2_2") (pintype "passive"))
      (node (ref "C126") (pin "2") (pinfunction "2_2") (pintype "passive"))
      (node (ref "C128") (pin "2") (pinfunction "2_2") (pintype "passive"))
      (node (ref "C129") (pin "2") (pinfunction "2_2") (pintype "passive"))
      (node (ref "C130") (pin "2") (pinfunction "2_2") (pintype "passive"))
      (node (ref "C131") (pin "2") (pinfunction "2_2") (pintype "passive"))
      (node (ref "C145") (pin "2") (pinfunction "2_2") (pintype "passive"))
      (node (ref "C93") (pin "2") (pinfunction "2_2") (pintype "passive"))
      (node (ref "C94") (pin "2") (pinfunction "2_2") (pintype "passive"))
      (node (ref "C95") (pin "2") (pinfunction "2_2") (pintype "passive"))
      (node (ref "C96") (pin "2") (pinfunction "2_2") (pintype "passive"))
      (node (ref "C97") (pin "2") (pinfunction "2_2") (pintype "passive"))
      (node (ref "C98") (pin "2") (pinfunction "2_2") (pintype "passive"))
      (node (ref "P6") (pin "3") (pinfunction "3_3") (pintype "passive"))
      (node (ref "Q4") (pin "2") (pinfunction "S_2") (pintype "passive"))
      (node (ref "Q5") (pin "2") (pinfunction "S_2") (pintype "passive"))
      (node (ref "R28") (pin "2") (pinfunction "2_2") (pintype "passive"))
      (node (ref "R33") (pin "1") (pinfunction "1_1") (pintype "passive"))
      (node (ref "R39") (pin "1") (pinfunction "1_1") (pintype "passive"))
      (node (ref "R40") (pin "2") (pinfunction "2_2") (pintype "passive"))
      (node (ref "U11") (pin "5") (pinfunction "GND_5") (pintype "power_in"))
      (node (ref "U12") (pin "5") (pinfunction "GND_5") (pintype "power_in"))
      (node (ref "U6") (pin "4") (pinfunction "GND_4") (pintype "power_in"))
      (node (ref "U7") (pin "4") (pinfunction "GND_4") (pintype "power_in"))
    )
    (net (code "26") (name "Net-(D4-Pad1)") (class "Default")
      (node (ref "D4") (pin "1") (pinfunction "1_1") (pintype "passive"))
      (node (ref "R29") (pin "2") (pinfunction "2_2") (pintype "passive"))
    )
    (net (code "27") (name "Net-(D5-Pad1)") (class "Default")
      (node (ref "D5") (pin "1") (pinfunction "1_1") (pintype "passive"))
      (node (ref "R35") (pin "2") (pinfunction "2_2") (pintype "passive"))
    )
    (net (code "28") (name "Net-(Q4-D)") (class "Default")
      (node (ref "D4") (pin "2") (pinfunction "2_2") (pintype "passive"))
      (node (ref "Q4") (pin "3") (pinfunction "D_3") (pintype "passive"))
    )
    (net (code "29") (name "Net-(Q5-D)") (class "Default")
      (node (ref "D5") (pin "2") (pinfunction "2_2") (pintype "passive"))
      (node (ref "Q5") (pin "3") (pinfunction "D_3") (pintype "passive"))
    )
    (net (code "30") (name "unconnected-(P5-Pad1)") (class "Default")
      (node (ref "P5") (pin "1") (pinfunction "1_1") (pintype "passive+no_connect"))
    )
    (net (code "31") (name "unconnected-(P6-Pad1)") (class "Default")
      (node (ref "P6") (pin "1") (pinfunction "1_1") (pintype "passive+no_connect"))
    )
    (net (code "32") (name "unconnected-(P7-Pad1)") (class "Default")
      (node (ref "P7") (pin "1") (pinfunction "1_1") (pintype "passive+no_connect"))
    )
    (net (code "33") (name "unconnected-(R34-Pad2)") (class "Default")
      (node (ref "R34") (pin "2") (pinfunction "2_2") (pintype "passive"))
    )
    (net (code "34") (name "unconnected-(U11-NC-Pad6)") (class "Default")
      (node (ref "U11") (pin "6") (pinfunction "NC_6") (pintype "tri_state+no_connect"))
    )
    (net (code "35") (name "unconnected-(U12-NC-Pad6)") (class "Default")
      (node (ref "U12") (pin "6") (pinfunction "NC_6") (pintype "tri_state+no_connect"))
    )
  )
)
